# berlingo_synth_0_5.net
KiCad netlist of a schematic drawn in EAGLE
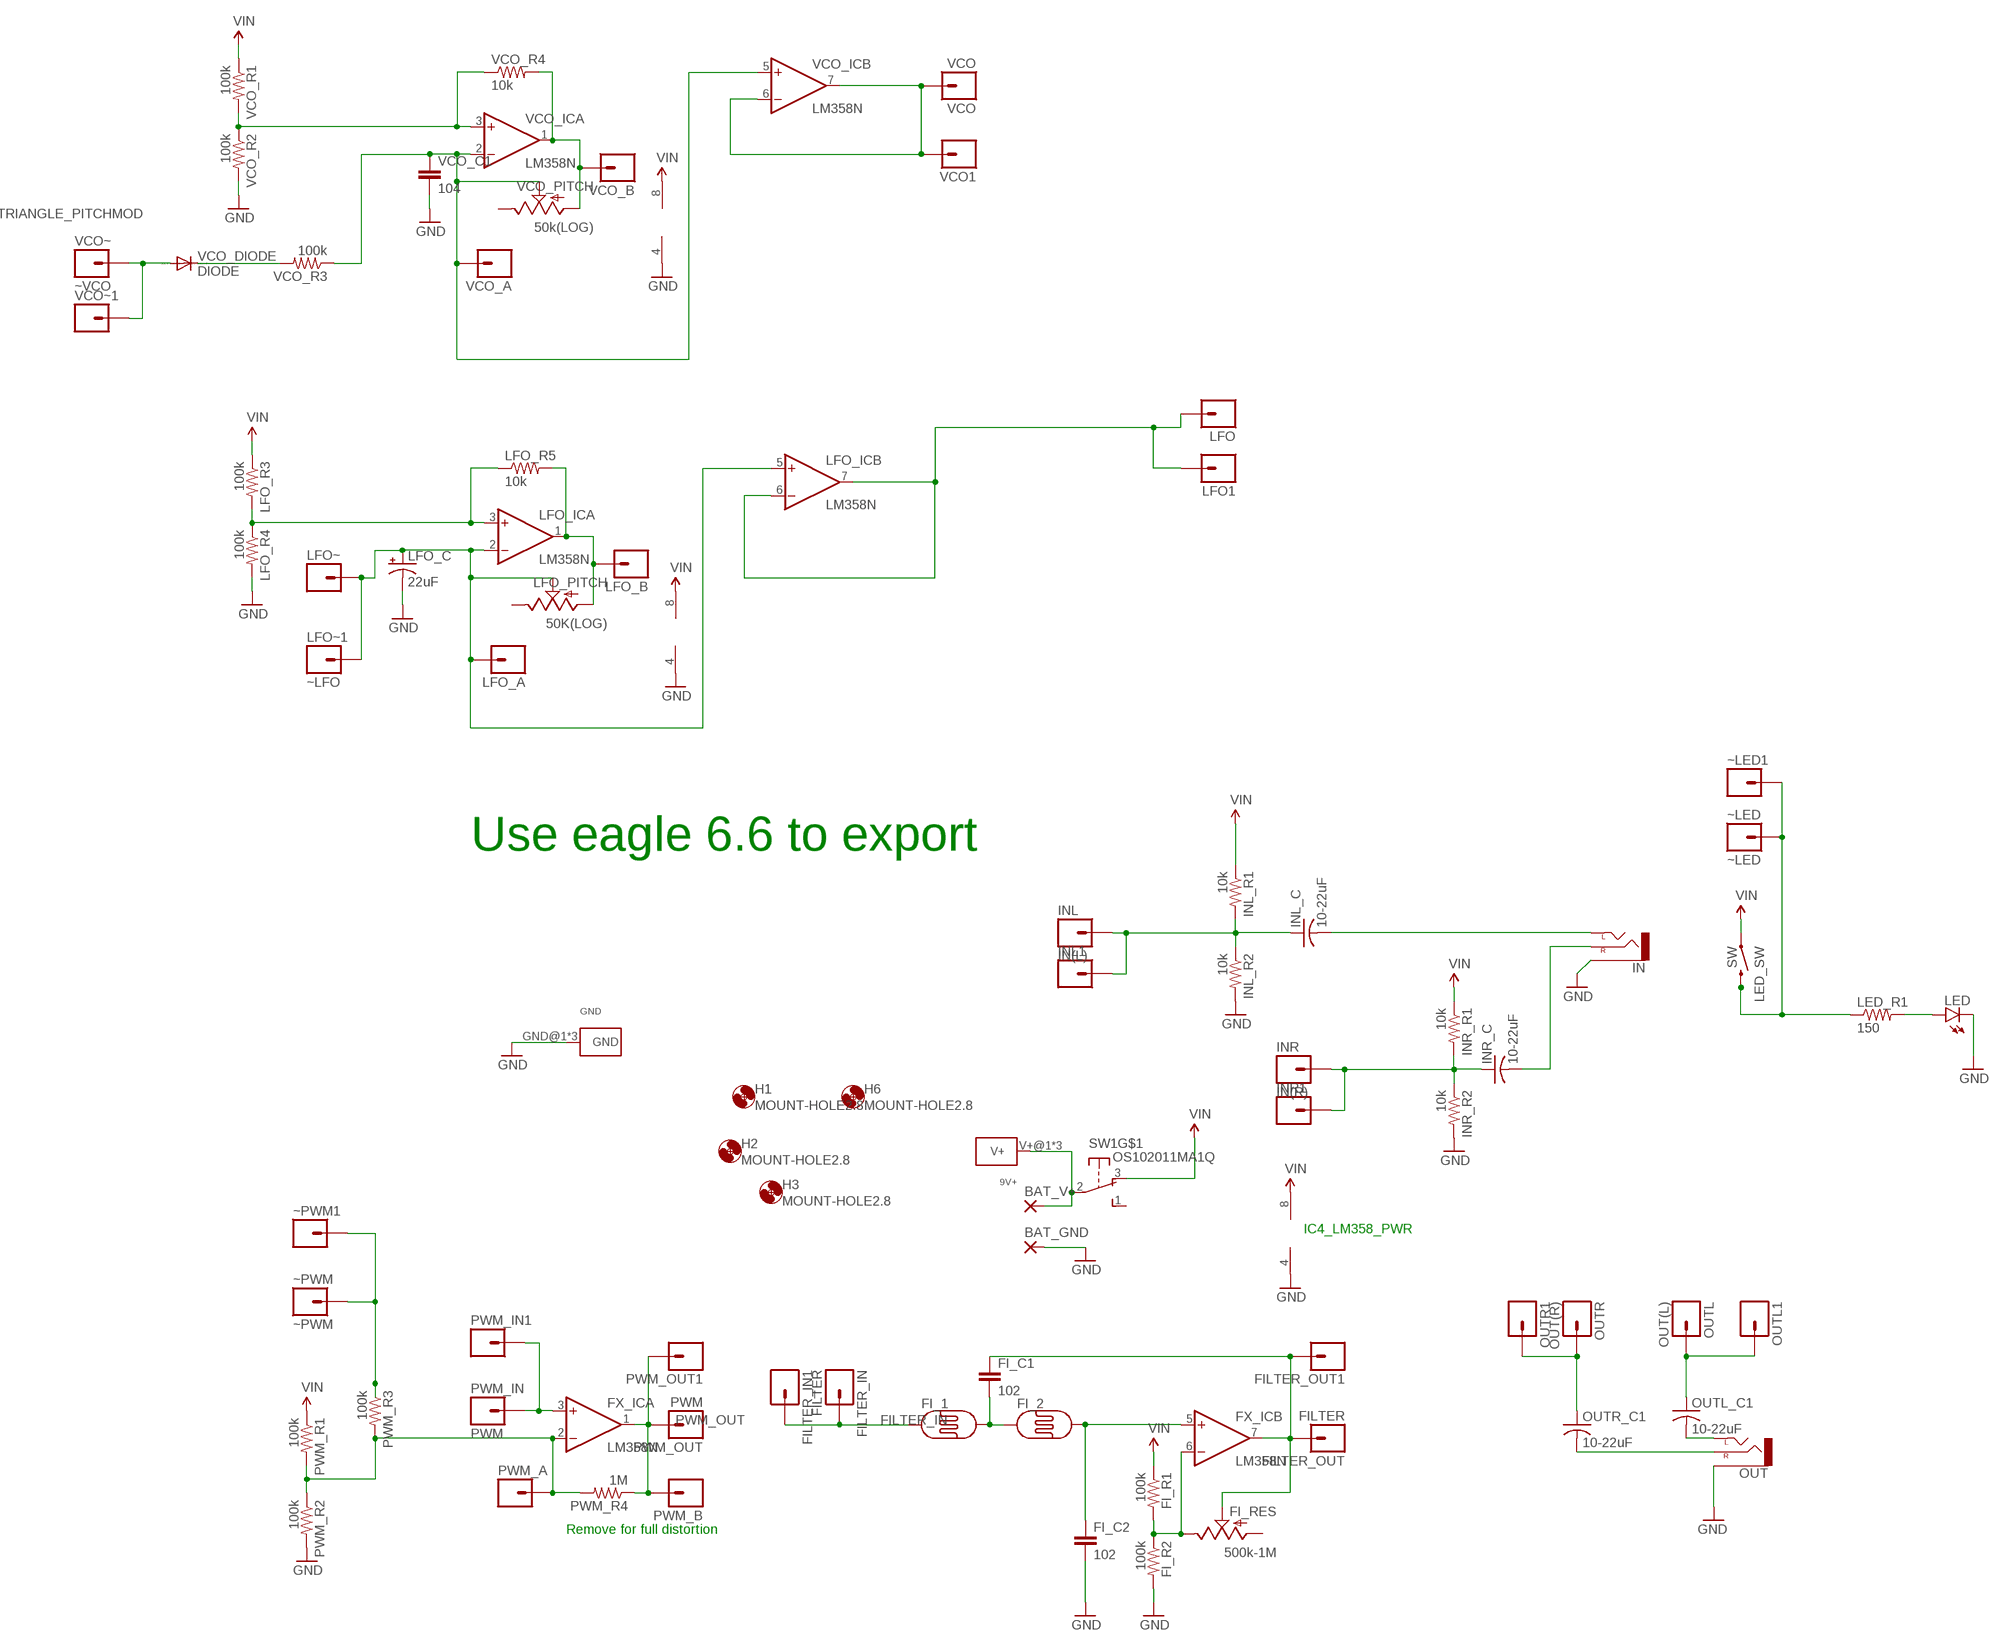
[diagram p0: schematic, sheet 1]

(export (version "E")
  (design (tool "Eeschema 10.0.6"))
  (components
    (comp (ref "9V+")
      (value "KEYSTONE-629+")
      (footprint "eagle-import:KEYSTONE_BATTAERY_TERMINAL-629+")
      (libsource (lib "eagle-import") (part "KEYSTONE-629+"))
    )
    (comp (ref "BAT_GND")
      (value "3,81/1,4")
      (footprint "eagle-import:3,81_1,4")
      (libsource (lib "eagle-import") (part "3,81/1,4"))
    )
    (comp (ref "BAT_V+")
      (value "3,81/1,4")
      (footprint "eagle-import:3,81_1,4")
      (libsource (lib "eagle-import") (part "3,81/1,4"))
    )
    (comp (ref "FILTER_IN")
      (value "FILTER")
      (footprint "eagle-import:1X01_SIDE_NAME")
      (libsource (lib "eagle-import") (part "HEADER-1X1"))
    )
    (comp (ref "FILTER_IN1")
      (value "HEADER-1X1")
      (footprint "eagle-import:1X01_SIDE_NAME")
      (libsource (lib "eagle-import") (part "HEADER-1X1"))
    )
    (comp (ref "FILTER_OUT")
      (value "FILTER")
      (footprint "eagle-import:1X01_SIDE_NAME")
      (libsource (lib "eagle-import") (part "HEADER-1X1"))
    )
    (comp (ref "FILTER_OUT1")
      (value "HEADER-1X1")
      (footprint "eagle-import:1X01_SIDE_NAME")
      (libsource (lib "eagle-import") (part "HEADER-1X1"))
    )
    (comp (ref "FI_1")
      (value "PHOTOCELLPTH")
      (footprint "eagle-import:PHOTOCELL")
      (libsource (lib "eagle-import") (part "PHOTOCELLPTH"))
    )
    (comp (ref "FI_2")
      (value "PHOTOCELLPTH")
      (footprint "eagle-import:PHOTOCELL")
      (libsource (lib "eagle-import") (part "PHOTOCELLPTH"))
    )
    (comp (ref "FI_C1")
      (value "102")
      (footprint "eagle-import:CAP-PTH-SMALLEZ")
      (libsource (lib "eagle-import") (part "CAPEZ"))
    )
    (comp (ref "FI_C2")
      (value "102")
      (footprint "eagle-import:CAP-PTH-SMALLEZ")
      (libsource (lib "eagle-import") (part "CAPEZ"))
    )
    (comp (ref "FI_R1")
      (value "100k")
      (footprint "eagle-import:0207_10")
      (libsource (lib "eagle-import") (part "R-US_0207/10"))
    )
    (comp (ref "FI_R2")
      (value "100k")
      (footprint "eagle-import:0207_10")
      (libsource (lib "eagle-import") (part "R-US_0207/10"))
    )
    (comp (ref "FI_RES")
      (value "500k-1M")
      (footprint "eagle-import:ALPS_POT")
      (libsource (lib "eagle-import") (part "POT"))
    )
    (comp (ref "FX_IC")
      (value "LM358N")
      (footprint "eagle-import:DIL08")
      (libsource (lib "eagle-import") (part "LM358N"))
    )
    (comp (ref "GND")
      (value "KEYSTONE-629")
      (footprint "eagle-import:KEYSTONE_AA_AAA_BATTERY_TERMINAL-629")
      (libsource (lib "eagle-import") (part "KEYSTONE-629"))
    )
    (comp (ref "H1")
      (value "MOUNT-HOLE2.8")
      (footprint "eagle-import:2,8")
      (libsource (lib "eagle-import") (part "MOUNT-HOLE2.8"))
    )
    (comp (ref "H2")
      (value "MOUNT-HOLE2.8")
      (footprint "eagle-import:2,8")
      (libsource (lib "eagle-import") (part "MOUNT-HOLE2.8"))
    )
    (comp (ref "H3")
      (value "MOUNT-HOLE2.8")
      (footprint "eagle-import:2,8")
      (libsource (lib "eagle-import") (part "MOUNT-HOLE2.8"))
    )
    (comp (ref "H6")
      (value "MOUNT-HOLE2.8")
      (footprint "eagle-import:2,8")
      (libsource (lib "eagle-import") (part "MOUNT-HOLE2.8"))
    )
    (comp (ref "IN")
      (value "AUDIO-JACKPTH")
      (footprint "eagle-import:AUDIO-JACK")
      (libsource (lib "eagle-import") (part "AUDIO-JACKPTH"))
    )
    (comp (ref "INL")
      (value "IN(L)")
      (footprint "eagle-import:1X01_SIDE_NAME")
      (libsource (lib "eagle-import") (part "HEADER-1X1"))
    )
    (comp (ref "INL1")
      (value "HEADER-1X1")
      (footprint "eagle-import:1X01_SIDE_NAME")
      (libsource (lib "eagle-import") (part "HEADER-1X1"))
    )
    (comp (ref "INL_C")
      (value "10-22uF")
      (footprint "eagle-import:C025-024X044")
      (libsource (lib "eagle-import") (part "C-US025-024X044"))
    )
    (comp (ref "INL_R1")
      (value "10k")
      (footprint "eagle-import:0207_10")
      (libsource (lib "eagle-import") (part "R-US_0207/10"))
    )
    (comp (ref "INL_R2")
      (value "10k")
      (footprint "eagle-import:0207_10")
      (libsource (lib "eagle-import") (part "R-US_0207/10"))
    )
    (comp (ref "INR")
      (value "IN(R)")
      (footprint "eagle-import:1X01_SIDE_NAME")
      (libsource (lib "eagle-import") (part "HEADER-1X1"))
    )
    (comp (ref "INR1")
      (value "HEADER-1X1")
      (footprint "eagle-import:1X01_SIDE_NAME")
      (libsource (lib "eagle-import") (part "HEADER-1X1"))
    )
    (comp (ref "INR_C")
      (value "10-22uF")
      (footprint "eagle-import:C025-024X044")
      (libsource (lib "eagle-import") (part "C-US025-024X044"))
    )
    (comp (ref "INR_R1")
      (value "10k")
      (footprint "eagle-import:0207_10")
      (libsource (lib "eagle-import") (part "R-US_0207/10"))
    )
    (comp (ref "INR_R2")
      (value "10k")
      (footprint "eagle-import:0207_10")
      (libsource (lib "eagle-import") (part "R-US_0207/10"))
    )
    (comp (ref "LED")
      (value "LED5MM")
      (footprint "eagle-import:LED5MM")
      (libsource (lib "eagle-import") (part "LED5MM"))
    )
    (comp (ref "LED_R1")
      (value "150")
      (footprint "eagle-import:0207_10")
      (libsource (lib "eagle-import") (part "R-US_0207/10"))
    )
    (comp (ref "LED_SW")
      (value "SW")
      (footprint "eagle-import:TACTILE-PTH-12MM")
      (libsource (lib "eagle-import") (part "SWITCH-MOMENTARY-212MM"))
    )
    (comp (ref "LFO")
      (value "HEADER-1X1")
      (footprint "eagle-import:1X01_SIDE_NAME")
      (libsource (lib "eagle-import") (part "HEADER-1X1"))
    )
    (comp (ref "LFO1")
      (value "HEADER-1X1")
      (footprint "eagle-import:1X01_SIDE_NAME")
      (libsource (lib "eagle-import") (part "HEADER-1X1"))
    )
    (comp (ref "LFO_A")
      (value "HEADER-1X1")
      (footprint "eagle-import:1X01_SIDE_NAME")
      (libsource (lib "eagle-import") (part "HEADER-1X1"))
    )
    (comp (ref "LFO_B")
      (value "HEADER-1X1")
      (footprint "eagle-import:1X01_SIDE_NAME")
      (libsource (lib "eagle-import") (part "HEADER-1X1"))
    )
    (comp (ref "LFO_C")
      (value "22uF")
      (footprint "eagle-import:E2,5-6")
      (libsource (lib "eagle-import") (part "CPOL-USE2.5-6"))
    )
    (comp (ref "LFO_IC")
      (value "LM358N")
      (footprint "eagle-import:DIL08")
      (libsource (lib "eagle-import") (part "LM358N"))
    )
    (comp (ref "LFO_PITCH")
      (value "50K(LOG)")
      (footprint "eagle-import:ALPS_POT")
      (libsource (lib "eagle-import") (part "POT"))
    )
    (comp (ref "LFO_R3")
      (value "100k")
      (footprint "eagle-import:0207_10")
      (libsource (lib "eagle-import") (part "R-US_0207/10"))
    )
    (comp (ref "LFO_R4")
      (value "100k")
      (footprint "eagle-import:0207_10")
      (libsource (lib "eagle-import") (part "R-US_0207/10"))
    )
    (comp (ref "LFO_R5")
      (value "10k")
      (footprint "eagle-import:0207_10")
      (libsource (lib "eagle-import") (part "R-US_0207/10"))
    )
    (comp (ref "LFO~")
      (value "HEADER-1X1")
      (footprint "eagle-import:1X01_SIDE_NAME")
      (libsource (lib "eagle-import") (part "HEADER-1X1"))
    )
    (comp (ref "LFO~1")
      (value "~LFO")
      (footprint "eagle-import:1X01_SIDE_NAME")
      (libsource (lib "eagle-import") (part "HEADER-1X1"))
    )
    (comp (ref "OUT")
      (value "AUDIO-JACKPTH")
      (footprint "eagle-import:AUDIO-JACK")
      (libsource (lib "eagle-import") (part "AUDIO-JACKPTH"))
    )
    (comp (ref "OUTL")
      (value "OUT(L)")
      (footprint "eagle-import:1X01_SIDE_NAME")
      (libsource (lib "eagle-import") (part "HEADER-1X1"))
    )
    (comp (ref "OUTL1")
      (value "HEADER-1X1")
      (footprint "eagle-import:1X01_SIDE_NAME")
      (libsource (lib "eagle-import") (part "HEADER-1X1"))
    )
    (comp (ref "OUTL_C1")
      (value "10-22uF")
      (footprint "eagle-import:C025-024X044")
      (libsource (lib "eagle-import") (part "C-US025-024X044"))
    )
    (comp (ref "OUTR")
      (value "OUT(R)")
      (footprint "eagle-import:1X01_SIDE_NAME")
      (libsource (lib "eagle-import") (part "HEADER-1X1"))
    )
    (comp (ref "OUTR1")
      (value "HEADER-1X1")
      (footprint "eagle-import:1X01_SIDE_NAME")
      (libsource (lib "eagle-import") (part "HEADER-1X1"))
    )
    (comp (ref "OUTR_C1")
      (value "10-22uF")
      (footprint "eagle-import:C025-024X044")
      (libsource (lib "eagle-import") (part "C-US025-024X044"))
    )
    (comp (ref "PWM_A")
      (value "HEADER-1X1")
      (footprint "eagle-import:1X01_SIDE_NAME")
      (libsource (lib "eagle-import") (part "HEADER-1X1"))
    )
    (comp (ref "PWM_B")
      (value "HEADER-1X1")
      (footprint "eagle-import:1X01_SIDE_NAME")
      (libsource (lib "eagle-import") (part "HEADER-1X1"))
    )
    (comp (ref "PWM_IN")
      (value "PWM")
      (footprint "eagle-import:1X01_SIDE_NAME")
      (libsource (lib "eagle-import") (part "HEADER-1X1"))
    )
    (comp (ref "PWM_IN1")
      (value "HEADER-1X1")
      (footprint "eagle-import:1X01_SIDE_NAME")
      (libsource (lib "eagle-import") (part "HEADER-1X1"))
    )
    (comp (ref "PWM_OUT")
      (value "PWM")
      (footprint "eagle-import:1X01_SIDE_NAME")
      (libsource (lib "eagle-import") (part "HEADER-1X1"))
    )
    (comp (ref "PWM_OUT1")
      (value "HEADER-1X1")
      (footprint "eagle-import:1X01_SIDE_NAME")
      (libsource (lib "eagle-import") (part "HEADER-1X1"))
    )
    (comp (ref "PWM_R1")
      (value "100k")
      (footprint "eagle-import:0207_10")
      (libsource (lib "eagle-import") (part "R-US_0207/10"))
    )
    (comp (ref "PWM_R2")
      (value "100k")
      (footprint "eagle-import:0207_10")
      (libsource (lib "eagle-import") (part "R-US_0207/10"))
    )
    (comp (ref "PWM_R3")
      (value "100k")
      (footprint "eagle-import:0207_10")
      (libsource (lib "eagle-import") (part "R-US_0207/10"))
    )
    (comp (ref "PWM_R4")
      (value "1M")
      (footprint "eagle-import:0207_10")
      (libsource (lib "eagle-import") (part "R-US_0207/10"))
    )
    (comp (ref "SW1")
      (value "OS102011MA1Q")
      (footprint "eagle-import:OS102011MA1Q")
      (libsource (lib "eagle-import") (part "OS102011MA1Q"))
    )
    (comp (ref "VCO")
      (value "VCO")
      (footprint "eagle-import:1X01_SIDE_NAME")
      (libsource (lib "eagle-import") (part "HEADER-1X1"))
    )
    (comp (ref "VCO1")
      (value "HEADER-1X1")
      (footprint "eagle-import:1X01_SIDE_NAME")
      (libsource (lib "eagle-import") (part "HEADER-1X1"))
    )
    (comp (ref "VCO_A")
      (value "HEADER-1X1")
      (footprint "eagle-import:1X01_SIDE_NAME")
      (libsource (lib "eagle-import") (part "HEADER-1X1"))
    )
    (comp (ref "VCO_B")
      (value "HEADER-1X1")
      (footprint "eagle-import:1X01_SIDE_NAME")
      (libsource (lib "eagle-import") (part "HEADER-1X1"))
    )
    (comp (ref "VCO_C1")
      (value "104")
      (footprint "eagle-import:CAP-PTH-SMALLEZ")
      (libsource (lib "eagle-import") (part "CAPEZ"))
    )
    (comp (ref "VCO_DIODE")
      (value "DIODE")
      (footprint "eagle-import:DO41-10")
      (libsource (lib "eagle-import") (part "1N4004"))
    )
    (comp (ref "VCO_IC")
      (value "LM358N")
      (footprint "eagle-import:DIL08")
      (libsource (lib "eagle-import") (part "LM358N"))
    )
    (comp (ref "VCO_PITCH")
      (value "50k(LOG)")
      (footprint "eagle-import:ALPS_POT")
      (libsource (lib "eagle-import") (part "POT"))
    )
    (comp (ref "VCO_R1")
      (value "100k")
      (footprint "eagle-import:0207_10")
      (libsource (lib "eagle-import") (part "R-US_0207/10"))
    )
    (comp (ref "VCO_R2")
      (value "100k")
      (footprint "eagle-import:0207_10")
      (libsource (lib "eagle-import") (part "R-US_0207/10"))
    )
    (comp (ref "VCO_R3")
      (value "100k")
      (footprint "eagle-import:0207_10")
      (libsource (lib "eagle-import") (part "R-US_0207/10"))
    )
    (comp (ref "VCO_R4")
      (value "10k")
      (footprint "eagle-import:0207_10")
      (libsource (lib "eagle-import") (part "R-US_0207/10"))
    )
    (comp (ref "VCO~")
      (value "~VCO")
      (footprint "eagle-import:1X01_SIDE_NAME")
      (libsource (lib "eagle-import") (part "HEADER-1X1"))
    )
    (comp (ref "VCO~1")
      (value "HEADER-1X1")
      (footprint "eagle-import:1X01_SIDE_NAME")
      (libsource (lib "eagle-import") (part "HEADER-1X1"))
    )
    (comp (ref "~LED")
      (value "~LED")
      (footprint "eagle-import:1X01_SIDE_NAME")
      (libsource (lib "eagle-import") (part "HEADER-1X1"))
    )
    (comp (ref "~LED1")
      (value "HEADER-1X1")
      (footprint "eagle-import:1X01_SIDE_NAME")
      (libsource (lib "eagle-import") (part "HEADER-1X1"))
    )
    (comp (ref "~PWM")
      (value "~PWM")
      (footprint "eagle-import:1X01_SIDE_NAME")
      (libsource (lib "eagle-import") (part "HEADER-1X1"))
    )
    (comp (ref "~PWM1")
      (value "HEADER-1X1")
      (footprint "eagle-import:1X01_SIDE_NAME")
      (libsource (lib "eagle-import") (part "HEADER-1X1"))
    )
  )
  (nets
    (net (code "1") (name "/FILTER_IN") (class "Default")
      (node (ref "FILTER_IN") (pin "1") (pinfunction "1_1") (pintype "passive"))
      (node (ref "FILTER_IN1") (pin "1") (pinfunction "1_1") (pintype "passive"))
      (node (ref "FI_1") (pin "1") (pinfunction "P$1_1") (pintype "bidirectional"))
    )
    (net (code "2") (name "/PWM_OUT") (class "Default")
      (node (ref "FX_IC") (pin "1") (pinfunction "OUT_1") (pintype "output"))
      (node (ref "PWM_B") (pin "1") (pinfunction "1_1") (pintype "passive"))
      (node (ref "PWM_OUT") (pin "1") (pinfunction "1_1") (pintype "passive"))
      (node (ref "PWM_OUT1") (pin "1") (pinfunction "1_1") (pintype "passive"))
      (node (ref "PWM_R4") (pin "1") (pinfunction "1_1") (pintype "passive"))
    )
    (net (code "3") (name "/TRIANGLE_PITCHMOD") (class "Default")
      (node (ref "VCO_DIODE") (pin "A") (pinfunction "A_A") (pintype "passive"))
      (node (ref "VCO~") (pin "1") (pinfunction "1_1") (pintype "passive"))
      (node (ref "VCO~1") (pin "1") (pinfunction "1_1") (pintype "passive"))
    )
    (net (code "4") (name "GND") (class "Default")
      (node (ref "BAT_GND") (pin "1") (pinfunction "P_1") (pintype "passive"))
      (node (ref "FI_C2") (pin "2") (pinfunction "2_2") (pintype "passive"))
      (node (ref "FI_R2") (pin "2") (pinfunction "2_2") (pintype "passive"))
      (node (ref "FX_IC") (pin "4") (pinfunction "V-_4") (pintype "power_in"))
      (node (ref "GND") (pin "GND@1") (pinfunction "GND_GND@1") (pintype "power_in"))
      (node (ref "GND") (pin "GND@2") (pinfunction "GND_GND@2") (pintype "power_in"))
      (node (ref "GND") (pin "GND@3") (pinfunction "GND_GND@3") (pintype "power_in"))
      (node (ref "IN") (pin "SLEEVE") (pinfunction "SLEEVE_SLEEVE") (pintype "bidirectional"))
      (node (ref "INL_R2") (pin "2") (pinfunction "2_2") (pintype "passive"))
      (node (ref "INR_R2") (pin "2") (pinfunction "2_2") (pintype "passive"))
      (node (ref "LED") (pin "K") (pinfunction "C_K") (pintype "passive"))
      (node (ref "LFO_C") (pin "-") (pinfunction "-_-") (pintype "passive"))
      (node (ref "LFO_IC") (pin "4") (pinfunction "V-_4") (pintype "power_in"))
      (node (ref "LFO_R4") (pin "2") (pinfunction "2_2") (pintype "passive"))
      (node (ref "OUT") (pin "SLEEVE") (pinfunction "SLEEVE_SLEEVE") (pintype "bidirectional"))
      (node (ref "PWM_R2") (pin "2") (pinfunction "2_2") (pintype "passive"))
      (node (ref "VCO_C1") (pin "2") (pinfunction "2_2") (pintype "passive"))
      (node (ref "VCO_IC") (pin "4") (pinfunction "V-_4") (pintype "power_in"))
      (node (ref "VCO_R2") (pin "2") (pinfunction "2_2") (pintype "passive"))
    )
    (net (code "5") (name "Net-(BAT_V+-P)") (class "Default")
      (node (ref "9V+") (pin "V+@1") (pinfunction "V+_V+@1") (pintype "power_in"))
      (node (ref "9V+") (pin "V+@2") (pinfunction "V+_V+@2") (pintype "power_in"))
      (node (ref "9V+") (pin "V+@3") (pinfunction "V+_V+@3") (pintype "power_in"))
      (node (ref "BAT_V+") (pin "1") (pinfunction "P_1") (pintype "passive"))
      (node (ref "SW1") (pin "2") (pinfunction "P_2") (pintype "passive"))
    )
    (net (code "6") (name "Net-(FI_1-P$2)") (class "Default")
      (node (ref "FI_1") (pin "2") (pinfunction "P$2_2") (pintype "bidirectional"))
      (node (ref "FI_2") (pin "1") (pinfunction "P$1_1") (pintype "bidirectional"))
      (node (ref "FI_C1") (pin "2") (pinfunction "2_2") (pintype "passive"))
    )
    (net (code "7") (name "Net-(FI_2-P$2)") (class "Default")
      (node (ref "FI_2") (pin "2") (pinfunction "P$2_2") (pintype "bidirectional"))
      (node (ref "FI_C2") (pin "1") (pinfunction "1_1") (pintype "passive"))
      (node (ref "FX_IC") (pin "5") (pinfunction "+IN_5") (pintype "input"))
    )
    (net (code "8") (name "Net-(FI_RES-E)") (class "Default")
      (node (ref "FI_R1") (pin "2") (pinfunction "2_2") (pintype "passive"))
      (node (ref "FI_R2") (pin "1") (pinfunction "1_1") (pintype "passive"))
      (node (ref "FI_RES") (pin "P$1") (pinfunction "E_P$1") (pintype "passive"))
      (node (ref "FX_IC") (pin "6") (pinfunction "-IN_6") (pintype "input"))
    )
    (net (code "9") (name "Net-(FI_RES-S)") (class "Default")
      (node (ref "FILTER_OUT") (pin "1") (pinfunction "1_1") (pintype "passive"))
      (node (ref "FILTER_OUT1") (pin "1") (pinfunction "1_1") (pintype "passive"))
      (node (ref "FI_C1") (pin "1") (pinfunction "1_1") (pintype "passive"))
      (node (ref "FI_RES") (pin "P$2") (pinfunction "S_P$2") (pintype "passive"))
      (node (ref "FX_IC") (pin "7") (pinfunction "OUT_7") (pintype "output"))
    )
    (net (code "10") (name "Net-(FX_ICA-+IN)") (class "Default")
      (node (ref "FX_IC") (pin "3") (pinfunction "+IN_3") (pintype "input"))
      (node (ref "PWM_IN") (pin "1") (pinfunction "1_1") (pintype "passive"))
      (node (ref "PWM_IN1") (pin "1") (pinfunction "1_1") (pintype "passive"))
    )
    (net (code "11") (name "Net-(FX_ICA--IN)") (class "Default")
      (node (ref "FX_IC") (pin "2") (pinfunction "-IN_2") (pintype "input"))
      (node (ref "PWM_A") (pin "1") (pinfunction "1_1") (pintype "passive"))
      (node (ref "PWM_R1") (pin "2") (pinfunction "2_2") (pintype "passive"))
      (node (ref "PWM_R2") (pin "1") (pinfunction "1_1") (pintype "passive"))
      (node (ref "PWM_R3") (pin "2") (pinfunction "2_2") (pintype "passive"))
      (node (ref "PWM_R4") (pin "2") (pinfunction "2_2") (pintype "passive"))
    )
    (net (code "12") (name "Net-(IN-LEFT)") (class "Default")
      (node (ref "IN") (pin "TIP") (pinfunction "LEFT_TIP") (pintype "bidirectional"))
      (node (ref "INL_C") (pin "2") (pinfunction "2_2") (pintype "passive"))
    )
    (net (code "13") (name "Net-(IN-RIGHT)") (class "Default")
      (node (ref "IN") (pin "RING") (pinfunction "RIGHT_RING") (pintype "bidirectional"))
      (node (ref "INR_C") (pin "2") (pinfunction "2_2") (pintype "passive"))
    )
    (net (code "14") (name "Net-(INL-Pad1)") (class "Default")
      (node (ref "INL") (pin "1") (pinfunction "1_1") (pintype "passive"))
      (node (ref "INL1") (pin "1") (pinfunction "1_1") (pintype "passive"))
      (node (ref "INL_C") (pin "1") (pinfunction "1_1") (pintype "passive"))
      (node (ref "INL_R1") (pin "2") (pinfunction "2_2") (pintype "passive"))
      (node (ref "INL_R2") (pin "1") (pinfunction "1_1") (pintype "passive"))
    )
    (net (code "15") (name "Net-(INR-Pad1)") (class "Default")
      (node (ref "INR") (pin "1") (pinfunction "1_1") (pintype "passive"))
      (node (ref "INR1") (pin "1") (pinfunction "1_1") (pintype "passive"))
      (node (ref "INR_C") (pin "1") (pinfunction "1_1") (pintype "passive"))
      (node (ref "INR_R1") (pin "2") (pinfunction "2_2") (pintype "passive"))
      (node (ref "INR_R2") (pin "1") (pinfunction "1_1") (pintype "passive"))
    )
    (net (code "16") (name "Net-(LED-PadA)") (class "Default")
      (node (ref "LED") (pin "A") (pinfunction "A_A") (pintype "passive"))
      (node (ref "LED_R1") (pin "2") (pinfunction "2_2") (pintype "passive"))
    )
    (net (code "17") (name "Net-(LED_SW-2)") (class "Default")
      (node (ref "LED_R1") (pin "1") (pinfunction "1_1") (pintype "passive"))
      (node (ref "LED_SW") (pin "3") (pinfunction "2_3") (pintype "passive"))
      (node (ref "~LED") (pin "1") (pinfunction "1_1") (pintype "passive"))
      (node (ref "~LED1") (pin "1") (pinfunction "1_1") (pintype "passive"))
    )
    (net (code "18") (name "Net-(LFO_ICA-+IN)") (class "Default")
      (node (ref "LFO_IC") (pin "3") (pinfunction "+IN_3") (pintype "input"))
      (node (ref "LFO_R3") (pin "2") (pinfunction "2_2") (pintype "passive"))
      (node (ref "LFO_R4") (pin "1") (pinfunction "1_1") (pintype "passive"))
      (node (ref "LFO_R5") (pin "1") (pinfunction "1_1") (pintype "passive"))
    )
    (net (code "19") (name "Net-(LFO_ICA--IN)") (class "Default")
      (node (ref "LFO_A") (pin "1") (pinfunction "1_1") (pintype "passive"))
      (node (ref "LFO_C") (pin "+") (pinfunction "+_+") (pintype "passive"))
      (node (ref "LFO_IC") (pin "2") (pinfunction "-IN_2") (pintype "input"))
      (node (ref "LFO_IC") (pin "5") (pinfunction "+IN_5") (pintype "input"))
      (node (ref "LFO_PITCH") (pin "P$2") (pinfunction "S_P$2") (pintype "passive"))
      (node (ref "LFO~") (pin "1") (pinfunction "1_1") (pintype "passive"))
      (node (ref "LFO~1") (pin "1") (pinfunction "1_1") (pintype "passive"))
    )
    (net (code "20") (name "Net-(LFO_ICA-OUT)") (class "Default")
      (node (ref "LFO_B") (pin "1") (pinfunction "1_1") (pintype "passive"))
      (node (ref "LFO_IC") (pin "1") (pinfunction "OUT_1") (pintype "output"))
      (node (ref "LFO_PITCH") (pin "P$3") (pinfunction "A_P$3") (pintype "passive"))
      (node (ref "LFO_R5") (pin "2") (pinfunction "2_2") (pintype "passive"))
    )
    (net (code "21") (name "Net-(LFO_ICB--IN)") (class "Default")
      (node (ref "LFO") (pin "1") (pinfunction "1_1") (pintype "passive"))
      (node (ref "LFO1") (pin "1") (pinfunction "1_1") (pintype "passive"))
      (node (ref "LFO_IC") (pin "6") (pinfunction "-IN_6") (pintype "input"))
      (node (ref "LFO_IC") (pin "7") (pinfunction "OUT_7") (pintype "output"))
    )
    (net (code "22") (name "Net-(OUT-LEFT)") (class "Default")
      (node (ref "OUT") (pin "TIP") (pinfunction "LEFT_TIP") (pintype "bidirectional"))
      (node (ref "OUTL_C1") (pin "2") (pinfunction "2_2") (pintype "passive"))
    )
    (net (code "23") (name "Net-(OUT-RIGHT)") (class "Default")
      (node (ref "OUT") (pin "RING") (pinfunction "RIGHT_RING") (pintype "bidirectional"))
      (node (ref "OUTR_C1") (pin "2") (pinfunction "2_2") (pintype "passive"))
    )
    (net (code "24") (name "Net-(OUTL-Pad1)") (class "Default")
      (node (ref "OUTL") (pin "1") (pinfunction "1_1") (pintype "passive"))
      (node (ref "OUTL1") (pin "1") (pinfunction "1_1") (pintype "passive"))
      (node (ref "OUTL_C1") (pin "1") (pinfunction "1_1") (pintype "passive"))
    )
    (net (code "25") (name "Net-(OUTR-Pad1)") (class "Default")
      (node (ref "OUTR") (pin "1") (pinfunction "1_1") (pintype "passive"))
      (node (ref "OUTR1") (pin "1") (pinfunction "1_1") (pintype "passive"))
      (node (ref "OUTR_C1") (pin "1") (pinfunction "1_1") (pintype "passive"))
    )
    (net (code "26") (name "Net-(PWM_R3-Pad1)") (class "Default")
      (node (ref "PWM_R3") (pin "1") (pinfunction "1_1") (pintype "passive"))
      (node (ref "~PWM") (pin "1") (pinfunction "1_1") (pintype "passive"))
      (node (ref "~PWM1") (pin "1") (pinfunction "1_1") (pintype "passive"))
    )
    (net (code "27") (name "Net-(VCO_DIODE-PadC)") (class "Default")
      (node (ref "VCO_DIODE") (pin "C") (pinfunction "C_C") (pintype "passive"))
      (node (ref "VCO_R3") (pin "2") (pinfunction "2_2") (pintype "passive"))
    )
    (net (code "28") (name "Net-(VCO_ICA-+IN)") (class "Default")
      (node (ref "VCO_IC") (pin "3") (pinfunction "+IN_3") (pintype "input"))
      (node (ref "VCO_R1") (pin "2") (pinfunction "2_2") (pintype "passive"))
      (node (ref "VCO_R2") (pin "1") (pinfunction "1_1") (pintype "passive"))
      (node (ref "VCO_R4") (pin "1") (pinfunction "1_1") (pintype "passive"))
    )
    (net (code "29") (name "Net-(VCO_ICA--IN)") (class "Default")
      (node (ref "VCO_A") (pin "1") (pinfunction "1_1") (pintype "passive"))
      (node (ref "VCO_C1") (pin "1") (pinfunction "1_1") (pintype "passive"))
      (node (ref "VCO_IC") (pin "2") (pinfunction "-IN_2") (pintype "input"))
      (node (ref "VCO_IC") (pin "5") (pinfunction "+IN_5") (pintype "input"))
      (node (ref "VCO_PITCH") (pin "P$2") (pinfunction "S_P$2") (pintype "passive"))
      (node (ref "VCO_R3") (pin "1") (pinfunction "1_1") (pintype "passive"))
    )
    (net (code "30") (name "Net-(VCO_ICA-OUT)") (class "Default")
      (node (ref "VCO_B") (pin "1") (pinfunction "1_1") (pintype "passive"))
      (node (ref "VCO_IC") (pin "1") (pinfunction "OUT_1") (pintype "output"))
      (node (ref "VCO_PITCH") (pin "P$3") (pinfunction "A_P$3") (pintype "passive"))
      (node (ref "VCO_R4") (pin "2") (pinfunction "2_2") (pintype "passive"))
    )
    (net (code "31") (name "Net-(VCO_ICB--IN)") (class "Default")
      (node (ref "VCO") (pin "1") (pinfunction "1_1") (pintype "passive"))
      (node (ref "VCO1") (pin "1") (pinfunction "1_1") (pintype "passive"))
      (node (ref "VCO_IC") (pin "6") (pinfunction "-IN_6") (pintype "input"))
      (node (ref "VCO_IC") (pin "7") (pinfunction "OUT_7") (pintype "output"))
    )
    (net (code "32") (name "VIN") (class "Default")
      (node (ref "FI_R1") (pin "1") (pinfunction "1_1") (pintype "passive"))
      (node (ref "FX_IC") (pin "8") (pinfunction "V+_8") (pintype "power_in"))
      (node (ref "INL_R1") (pin "1") (pinfunction "1_1") (pintype "passive"))
      (node (ref "INR_R1") (pin "1") (pinfunction "1_1") (pintype "passive"))
      (node (ref "LED_SW") (pin "1") (pinfunction "1_1") (pintype "passive"))
      (node (ref "LFO_IC") (pin "8") (pinfunction "V+_8") (pintype "power_in"))
      (node (ref "LFO_R3") (pin "1") (pinfunction "1_1") (pintype "passive"))
      (node (ref "PWM_R1") (pin "1") (pinfunction "1_1") (pintype "passive"))
      (node (ref "SW1") (pin "3") (pinfunction "O_3") (pintype "passive"))
      (node (ref "VCO_IC") (pin "8") (pinfunction "V+_8") (pintype "power_in"))
      (node (ref "VCO_R1") (pin "1") (pinfunction "1_1") (pintype "passive"))
    )
    (net (code "33") (name "unconnected-(FI_RES-A-PadP$3)") (class "Default")
      (node (ref "FI_RES") (pin "P$3") (pinfunction "A_P$3") (pintype "passive"))
    )
    (net (code "34") (name "unconnected-(LFO_PITCH-E-PadP$1)") (class "Default")
      (node (ref "LFO_PITCH") (pin "P$1") (pinfunction "E_P$1") (pintype "passive"))
    )
    (net (code "35") (name "unconnected-(SW1A-S-Pad1)") (class "Default")
      (node (ref "SW1") (pin "1") (pinfunction "S_1") (pintype "passive"))
    )
    (net (code "36") (name "unconnected-(VCO_PITCH-E-PadP$1)") (class "Default")
      (node (ref "VCO_PITCH") (pin "P$1") (pinfunction "E_P$1") (pintype "passive"))
    )
  )
)
